# 4_Sensors.net
KiCad netlist of a schematic drawn in Altium Designer
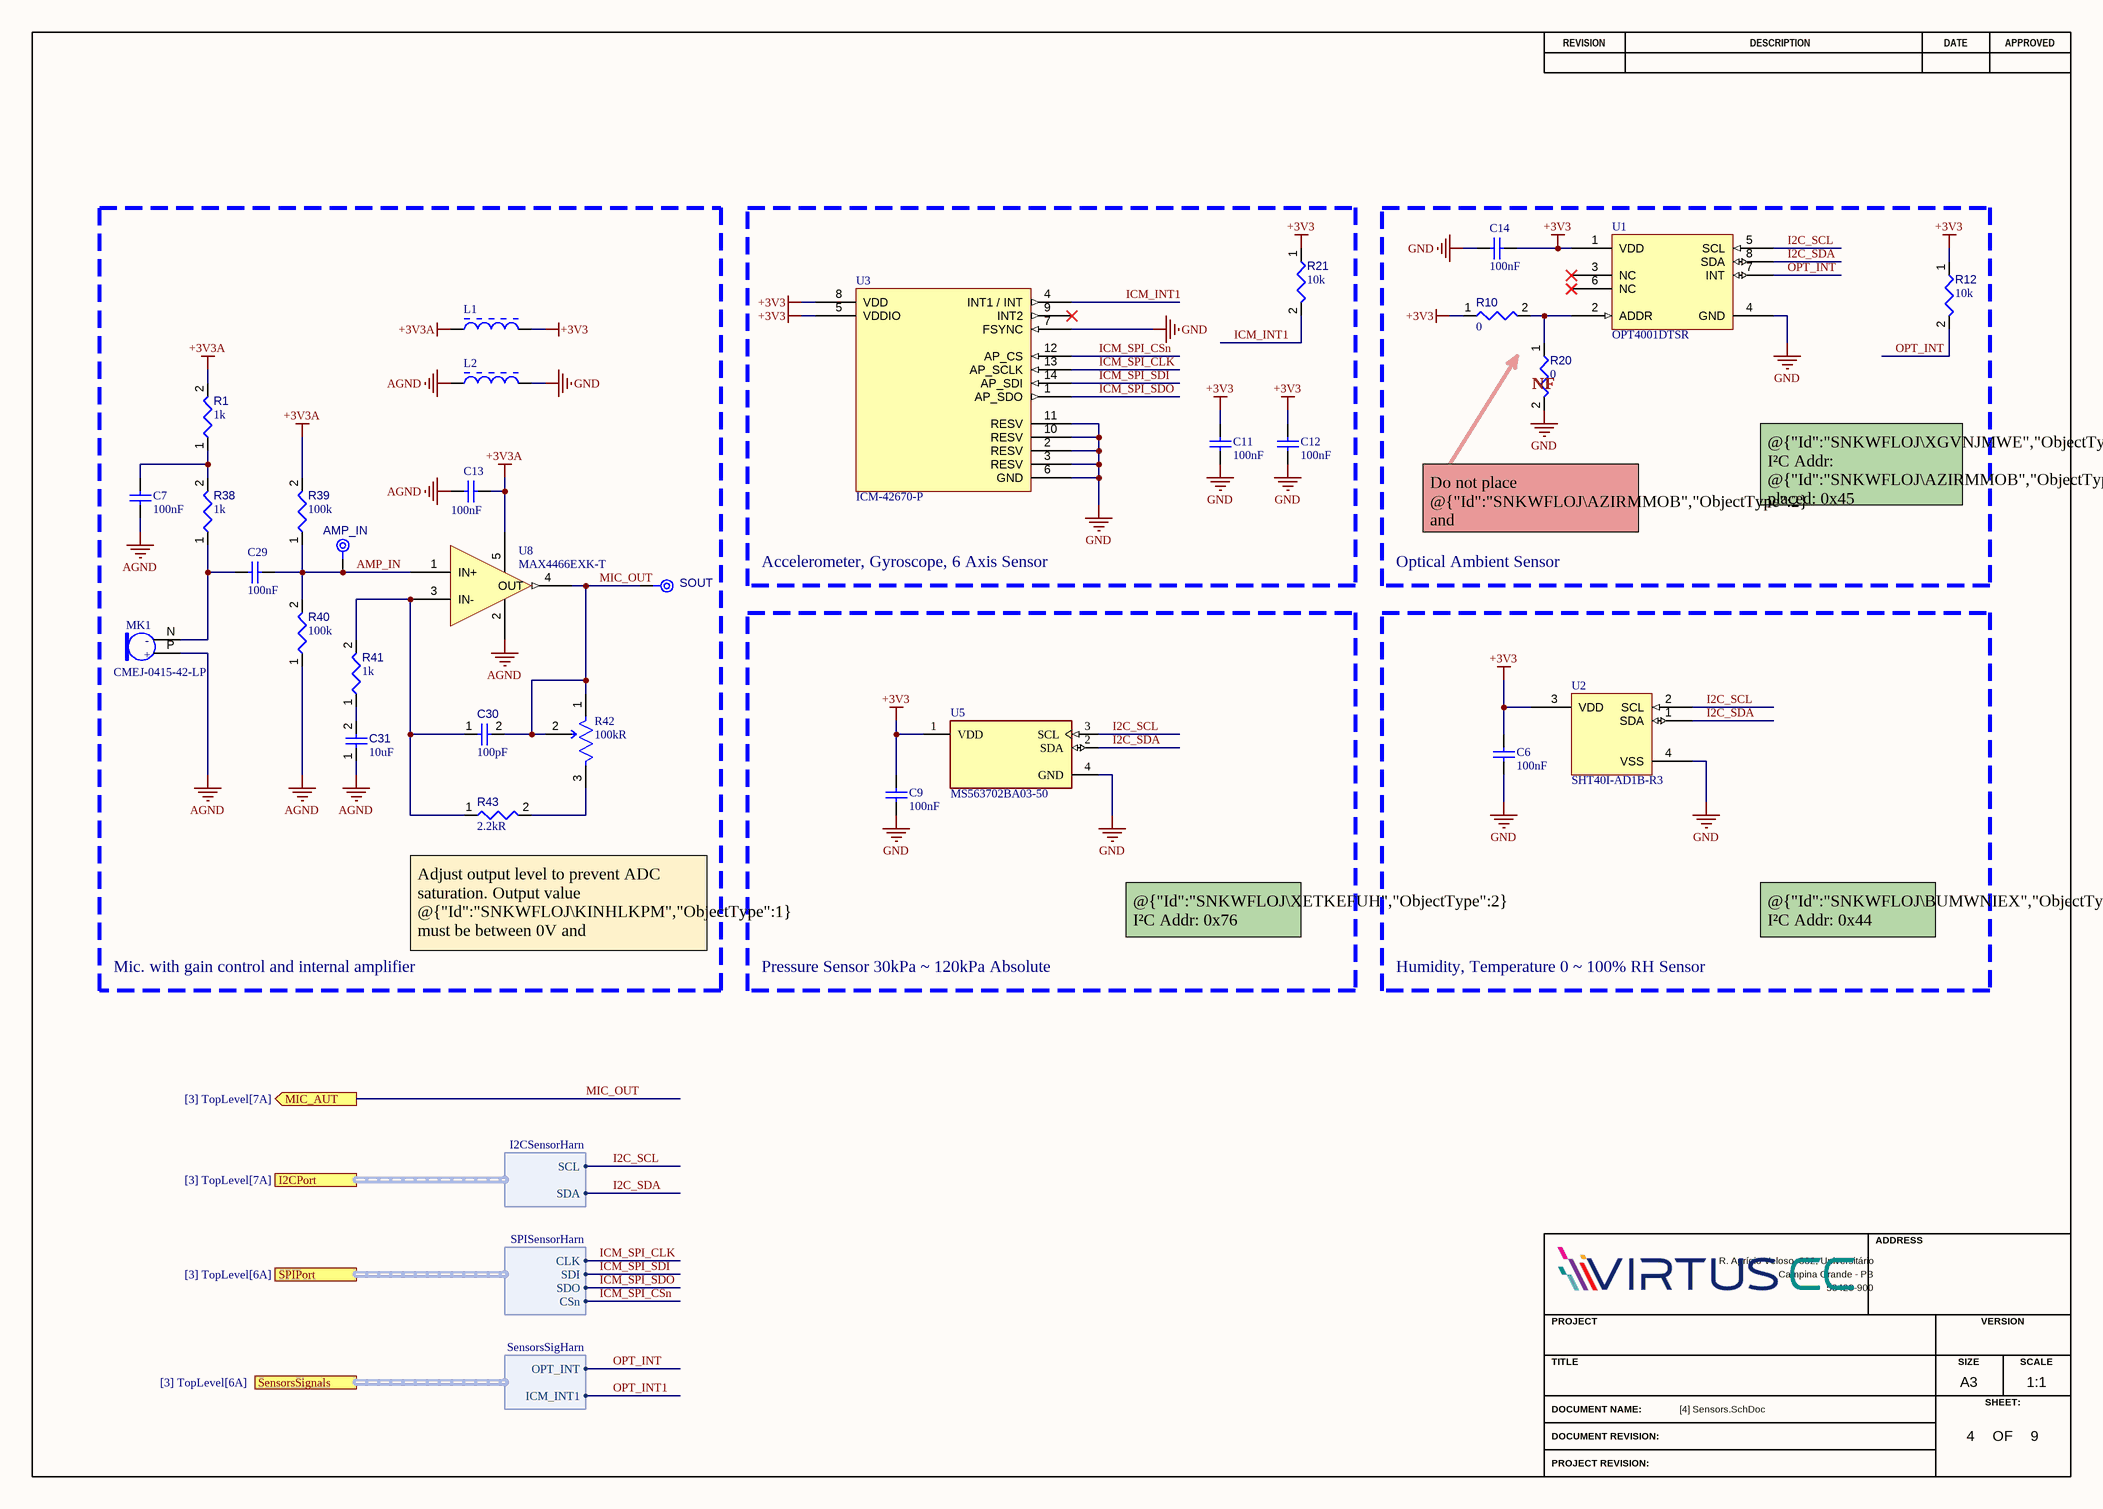
[diagram p0: [4] Sensors.SchDoc]

(export (version "E")
  (design (tool "Eeschema 10.0.6"))
  (components
    (comp (ref "AMP_IN")
      (value "TPAD6R")
      (footprint "TP06R")
      (description "0.6mm round")
      (libsource (lib "UFCG - Universidade Federal de Campina Grande") (part "CMP-001-0001-4"))
    )
    (comp (ref "C6")
      (value "100nF")
      (footprint "CAPC0603(1608)100_L")
      (description "Multilayer Ceramic Capacitor, 0.1 uF, 16 V, ± 20%, X7R, 0603 [1608 Metric]")
      (fields (field (name "TOLERANCE") "20%") (field (name "Comment") "VJ0603Y104MXJCW1BC"))
      (libsource (lib "UFCG - Universidade Federal de Campina Grande") (part "CAP"))
    )
    (comp (ref "C7")
      (value "100nF")
      (footprint "CAPC0603(1608)100_L")
      (description "Multilayer Ceramic Capacitor, 0.1 uF, 16 V, ± 20%, X7R, 0603 [1608 Metric]")
      (fields (field (name "TOLERANCE") "20%") (field (name "Comment") "VJ0603Y104MXJCW1BC"))
      (libsource (lib "UFCG - Universidade Federal de Campina Grande") (part "CAP"))
    )
    (comp (ref "C9")
      (value "100nF")
      (footprint "CAPC0603(1608)100_L")
      (description "Multilayer Ceramic Capacitor, 0.1 uF, 16 V, ± 20%, X7R, 0603 [1608 Metric]")
      (fields (field (name "TOLERANCE") "20%") (field (name "Comment") "VJ0603Y104MXJCW1BC"))
      (libsource (lib "UFCG - Universidade Federal de Campina Grande") (part "CAP"))
    )
    (comp (ref "C11")
      (value "100nF")
      (footprint "CAPC0603(1608)100_L")
      (description "Multilayer Ceramic Capacitor, 0.1 uF, 16 V, ± 20%, X7R, 0603 [1608 Metric]")
      (fields (field (name "TOLERANCE") "20%") (field (name "Comment") "VJ0603Y104MXJCW1BC"))
      (libsource (lib "UFCG - Universidade Federal de Campina Grande") (part "CAP"))
    )
    (comp (ref "C12")
      (value "100nF")
      (footprint "CAPC0603(1608)100_L")
      (description "Multilayer Ceramic Capacitor, 0.1 uF, 16 V, ± 20%, X7R, 0603 [1608 Metric]")
      (fields (field (name "TOLERANCE") "20%") (field (name "Comment") "VJ0603Y104MXJCW1BC"))
      (libsource (lib "UFCG - Universidade Federal de Campina Grande") (part "CAP"))
    )
    (comp (ref "C13")
      (value "100nF")
      (footprint "CAPC0603(1608)100_L")
      (description "Multilayer Ceramic Capacitor, 0.1 uF, 16 V, ± 20%, X7R, 0603 [1608 Metric]")
      (fields (field (name "TOLERANCE") "20%") (field (name "Comment") "VJ0603Y104MXJCW1BC"))
      (libsource (lib "UFCG - Universidade Federal de Campina Grande") (part "CAP"))
    )
    (comp (ref "C14")
      (value "100nF")
      (footprint "CAPC0603(1608)100_L")
      (description "Multilayer Ceramic Capacitor, 0.1 uF, 16 V, ± 20%, X7R, 0603 [1608 Metric]")
      (fields (field (name "TOLERANCE") "20%") (field (name "Comment") "VJ0603Y104MXJCW1BC"))
      (libsource (lib "UFCG - Universidade Federal de Campina Grande") (part "CAP"))
    )
    (comp (ref "C29")
      (value "100nF")
      (footprint "CAPC0603(1608)100_L")
      (description "Multilayer Ceramic Capacitor, 0.1 uF, 16 V, ± 20%, X7R, 0603 [1608 Metric]")
      (fields (field (name "TOLERANCE") "20%") (field (name "Comment") "VJ0603Y104MXJCW1BC"))
      (libsource (lib "UFCG - Universidade Federal de Campina Grande") (part "CAP"))
    )
    (comp (ref "C30")
      (value "100pF")
      (footprint "CAPC0603(1608)100_L")
      (description "Multilayer Ceramic Capacitor, 100 pF, 50 V, ï¿½ 10%, C0G (NP0), 0603 [1608 Metric]")
      (fields (field (name "TOLERANCE") "10%") (field (name "Comment") "C0603C101K5GACTU"))
      (libsource (lib "UFCG - Universidade Federal de Campina Grande") (part "CAP-NP-2"))
    )
    (comp (ref "C31")
      (value "10uF")
      (footprint "CAPC0603(1608)100_L")
      (description "Multilayer Ceramic Capacitor, 10 uF, 6.3 V, ± 20%, X5R, 0603 [1608 Metric]")
      (fields (field (name "TOLERANCE") "20%") (field (name "Comment") "GRM188R60J106ME47D"))
      (libsource (lib "UFCG - Universidade Federal de Campina Grande") (part "CAP-NP-2"))
    )
    (comp (ref "L1")
      (value "BLM21PG331SN1D")
      (footprint "INDC2013X105X50ML20T20")
      (fields (field (name "MANUFACTURER") "Murata") (field (name "TOLERANCE") "25%"))
      (libsource (lib "UFCG - Universidade Federal de Campina Grande") (part "IND-FB-2"))
    )
    (comp (ref "L2")
      (value "BLM21PG331SN1D")
      (footprint "INDC2013X105X50ML20T20")
      (fields (field (name "MANUFACTURER") "Murata") (field (name "TOLERANCE") "25%"))
      (libsource (lib "UFCG - Universidade Federal de Campina Grande") (part "IND-FB-2"))
    )
    (comp (ref "MK1")
      (value "CMEJ-0415-42-LP")
      (footprint "MIC_CMEJ-0415-42-LP")
      (description "4.0 mm, Omnidirectional, PCB Mount, 2.0 Vdc, Elecret Condenser Microphone")
      (fields (field (name "MF") "{'manufacturer': u'CUI'}"))
      (libsource (lib "UFCG - Universidade Federal de Campina Grande") (part "CMEJ-0415-42-LP"))
    )
    (comp (ref "R1")
      (value "1k")
      (footprint "RESC0603(1608)_L")
      (description "Chip Resistor, 1 KOhm, +/-1%, 0.1 W, -55 to 155 degC, 0603 (1608 Metric)")
      (fields (field (name "POWER") "100mW") (field (name "TOLERANCE") "1%"))
      (libsource (lib "UFCG - Universidade Federal de Campina Grande") (part "RES-2"))
    )
    (comp (ref "R10")
      (value "0")
      (footprint "RESC0603(1608)_L")
      (description "Chip Resistor, 0 Ohm, 0.1 W, -55 to 155 degC, 0603 (1608 Metric)")
      (fields (field (name "TOLERANCE") "5%") (field (name "POWER") "100mW"))
      (libsource (lib "UFCG - Universidade Federal de Campina Grande") (part "RES-2"))
    )
    (comp (ref "R12")
      (value "10k")
      (footprint "RESC0603(1608)_L")
      (description "Chip Resistor, 10 KOhm, +/- 1%, 01 W, -55 to 155 degC, 0603 (1608 Metric)")
      (fields (field (name "POWER") "100mW") (field (name "TOLERANCE") "1%"))
      (libsource (lib "UFCG - Universidade Federal de Campina Grande") (part "RES-2"))
    )
    (comp (ref "R20")
      (value "0")
      (footprint "RESC0603(1608)_L")
      (description "Chip Resistor, 0 Ohm, 0.1 W, -55 to 155 degC, 0603 (1608 Metric)")
      (fields (field (name "TOLERANCE") "5%") (field (name "POWER") "100mW"))
      (libsource (lib "UFCG - Universidade Federal de Campina Grande") (part "RES-2"))
    )
    (comp (ref "R21")
      (value "10k")
      (footprint "RESC0603(1608)_L")
      (description "Chip Resistor, 10 KOhm, +/- 1%, 01 W, -55 to 155 degC, 0603 (1608 Metric)")
      (fields (field (name "POWER") "100mW") (field (name "TOLERANCE") "1%"))
      (libsource (lib "UFCG - Universidade Federal de Campina Grande") (part "RES-2"))
    )
    (comp (ref "R38")
      (value "1k")
      (footprint "RESC0603(1608)_L")
      (description "Chip Resistor, 1 KOhm, +/-1%, 0.1 W, -55 to 155 degC, 0603 (1608 Metric)")
      (fields (field (name "POWER") "100mW") (field (name "TOLERANCE") "1%"))
      (libsource (lib "UFCG - Universidade Federal de Campina Grande") (part "RES-2"))
    )
    (comp (ref "R39")
      (value "100k")
      (footprint "RESC0603(1608)_L")
      (description "Chip Resistor, 100 KOhm, +/- 1%, 0.1 W, -55 to 155 degC, 0603 (1608 Metric)")
      (fields (field (name "TOLERANCE") "1%") (field (name "POWER") "100mW"))
      (libsource (lib "UFCG - Universidade Federal de Campina Grande") (part "RES-2"))
    )
    (comp (ref "R40")
      (value "100k")
      (footprint "RESC0603(1608)_L")
      (description "Chip Resistor, 100 KOhm, +/- 1%, 0.1 W, -55 to 155 degC, 0603 (1608 Metric)")
      (fields (field (name "TOLERANCE") "1%") (field (name "POWER") "100mW"))
      (libsource (lib "UFCG - Universidade Federal de Campina Grande") (part "RES-2"))
    )
    (comp (ref "R41")
      (value "1k")
      (footprint "RESC0603(1608)_L")
      (description "Chip Resistor, 1 KOhm, +/-1%, 0.1 W, -55 to 155 degC, 0603 (1608 Metric)")
      (fields (field (name "POWER") "100mW") (field (name "TOLERANCE") "1%"))
      (libsource (lib "UFCG - Universidade Federal de Campina Grande") (part "RES-2"))
    )
    (comp (ref "R42")
      (value "100kR")
      (footprint "FP-TC33X-2-MFG")
      (description "Cermet trimmer potentiometer, 100 kΩ, 0.1 W, SMD, on top, TC33X-2-104E")
      (fields (field (name "TOLERANCE") "25%") (field (name "Comment") "TC33X-2-104E"))
      (libsource (lib "UFCG - Universidade Federal de Campina Grande") (part "13357d81287629c2fd191d242cfa50c"))
    )
    (comp (ref "R43")
      (value "2.2kR")
      (footprint "RESC0603(1608)_L")
      (description "SMD Chip Resistor, 2.2 kOhm, ± 1%, 100 mW, 0603 [1608 Metric], Thick Film, General Purpose")
      (fields (field (name "TOLERANCE") "1%") (field (name "Comment") "CRCW06032K20FKEA"))
      (libsource (lib "UFCG - Universidade Federal de Campina Grande") (part "RES-2"))
    )
    (comp (ref "SOUT")
      (value "TPAD6R")
      (footprint "TP06R")
      (description "0.6mm round")
      (libsource (lib "UFCG - Universidade Federal de Campina Grande") (part "CMP-001-0001-4"))
    )
    (comp (ref "U1")
      (value "OPT4001DTSR")
      (footprint "SON50P130X60-8N")
      (description "High-speed high-precision digital ambient light sensor (ALS) 8-SOT-5X3 -40 to 85")
      (libsource (lib "UFCG - Universidade Federal de Campina Grande") (part "New symbol 1"))
    )
    (comp (ref "U2")
      (value "SHT40I-AD1B-R3")
      (footprint "QFN80P150X150X55-4N")
      (description "Humidity And Temperature Sensor")
      (libsource (lib "UFCG - Universidade Federal de Campina Grande") (part "SHT40I-AD1B-R3"))
    )
    (comp (ref "U3")
      (value "ICM-42670-P")
      (footprint "QFN50P300X250X81-14N")
      (description "Mems Module, 1.71-3.6 V, Lga-14 Rohs Compliant: Yes")
      (libsource (lib "UFCG - Universidade Federal de Campina Grande") (part "ICM-42670-P"))
    )
    (comp (ref "U5")
      (value "MS563702BA03-50")
      (footprint "FP-MS563702BA03-50-MFG")
      (description "Pressure Sensor, Barometric, 300 mbar, 1200 mbar, QFN, 8, -40 C")
      (libsource (lib "UFCG - Universidade Federal de Campina Grande") (part "74709a9a55dd6d6ee219151e6d8b12f"))
    )
    (comp (ref "U8")
      (value "MAX4466EXK-T")
      (footprint "SOT65P200X110-5N")
      (description "Audio Amp Microphone 1-CH Mono Class-AB 5-Pin SC-70 T/R")
      (libsource (lib "UFCG - Universidade Federal de Campina Grande") (part "MAX4466EXK-T"))
    )
  )
  (nets
    (net (code "4") (name "+3V3") (class "Default")
      (node (ref "C11") (pin "2") (pinfunction "2_2") (pintype "passive"))
      (node (ref "C12") (pin "2") (pinfunction "2_2") (pintype "passive"))
      (node (ref "C14") (pin "2") (pinfunction "2_2") (pintype "passive"))
      (node (ref "C6") (pin "2") (pinfunction "2_2") (pintype "passive"))
      (node (ref "C9") (pin "2") (pinfunction "2_2") (pintype "passive"))
      (node (ref "L1") (pin "2") (pinfunction "2_2") (pintype "passive"))
      (node (ref "R10") (pin "1") (pinfunction "1_1") (pintype "passive"))
      (node (ref "R12") (pin "1") (pinfunction "1_1") (pintype "passive"))
      (node (ref "R21") (pin "1") (pinfunction "1_1") (pintype "passive"))
      (node (ref "U1") (pin "1") (pinfunction "VDD_1") (pintype "power_in"))
      (node (ref "U2") (pin "3") (pinfunction "VDD_3") (pintype "power_in"))
      (node (ref "U3") (pin "5") (pinfunction "VDDIO_5") (pintype "power_in"))
      (node (ref "U3") (pin "8") (pinfunction "VDD_8") (pintype "power_in"))
      (node (ref "U5") (pin "1") (pinfunction "VDD_1") (pintype "power_in"))
    )
    (net (code "5") (name "+3V3A") (class "Default")
      (node (ref "C13") (pin "2") (pinfunction "2_2") (pintype "passive"))
      (node (ref "L1") (pin "1") (pinfunction "1_1") (pintype "passive"))
      (node (ref "R1") (pin "2") (pinfunction "2_2") (pintype "passive"))
      (node (ref "R39") (pin "2") (pinfunction "2_2") (pintype "passive"))
      (node (ref "U8") (pin "5") (pinfunction "VCC_5") (pintype "power_in"))
    )
    (net (code "6") (name "/AMP_IN") (class "Default")
      (node (ref "AMP_IN") (pin "1") (pinfunction "TP_1") (pintype "passive"))
      (node (ref "C29") (pin "2") (pinfunction "2_2") (pintype "passive"))
      (node (ref "R39") (pin "1") (pinfunction "1_1") (pintype "passive"))
      (node (ref "R40") (pin "2") (pinfunction "2_2") (pintype "passive"))
      (node (ref "U8") (pin "1") (pinfunction "IN+_1") (pintype "passive"))
    )
    (net (code "7") (name "/I2C_SCL") (class "Default")
      (node (ref "U1") (pin "5") (pinfunction "SCL_5") (pintype "input"))
      (node (ref "U2") (pin "2") (pinfunction "SCL_2") (pintype "input"))
      (node (ref "U5") (pin "3") (pinfunction "SCL_3") (pintype "input"))
    )
    (net (code "8") (name "/I2C_SDA") (class "Default")
      (node (ref "U1") (pin "8") (pinfunction "SDA_8") (pintype "bidirectional"))
      (node (ref "U2") (pin "1") (pinfunction "SDA_1") (pintype "bidirectional"))
      (node (ref "U5") (pin "2") (pinfunction "SDA_2") (pintype "bidirectional"))
    )
    (net (code "9") (name "/ICM_INT1") (class "Default")
      (node (ref "R21") (pin "2") (pinfunction "2_2") (pintype "passive"))
      (node (ref "U3") (pin "4") (pinfunction "INT1_/_INT_4") (pintype "output"))
    )
    (net (code "10") (name "/ICM_SPI_CLK") (class "Default")
      (node (ref "U3") (pin "13") (pinfunction "AP_SCLK_13") (pintype "input"))
    )
    (net (code "11") (name "/ICM_SPI_CSn") (class "Default")
      (node (ref "U3") (pin "12") (pinfunction "AP_CS_12") (pintype "input"))
    )
    (net (code "12") (name "/ICM_SPI_SDI") (class "Default")
      (node (ref "U3") (pin "14") (pinfunction "AP_SDI_14") (pintype "input"))
    )
    (net (code "13") (name "/ICM_SPI_SDO") (class "Default")
      (node (ref "U3") (pin "1") (pinfunction "AP_SDO_1") (pintype "output"))
    )
    (net (code "14") (name "/MIC_OUT") (class "Default")
      (node (ref "C30") (pin "2") (pinfunction "2_2") (pintype "passive"))
      (node (ref "R42") (pin "1") (pinfunction "CCW_1") (pintype "passive"))
      (node (ref "R42") (pin "2") (pinfunction "WIPER_2") (pintype "passive"))
      (node (ref "SOUT") (pin "1") (pinfunction "TP_1") (pintype "passive"))
      (node (ref "U8") (pin "4") (pinfunction "OUT_4") (pintype "output"))
    )
    (net (code "15") (name "/OPT_INT") (class "Default")
      (node (ref "R12") (pin "2") (pinfunction "2_2") (pintype "passive"))
      (node (ref "U1") (pin "7") (pinfunction "INT_7") (pintype "bidirectional"))
    )
    (net (code "20") (name "AGND") (class "Default")
      (node (ref "C13") (pin "1") (pinfunction "1_1") (pintype "passive"))
      (node (ref "C31") (pin "1") (pinfunction "1_1") (pintype "passive"))
      (node (ref "C7") (pin "1") (pinfunction "1_1") (pintype "passive"))
      (node (ref "L2") (pin "1") (pinfunction "1_1") (pintype "passive"))
      (node (ref "MK1") (pin "P") (pinfunction "OUTPUT_P") (pintype "passive"))
      (node (ref "R40") (pin "1") (pinfunction "1_1") (pintype "passive"))
      (node (ref "U8") (pin "2") (pinfunction "GND_2") (pintype "power_in"))
    )
    (net (code "21") (name "GND") (class "Default")
      (node (ref "C11") (pin "1") (pinfunction "1_1") (pintype "passive"))
      (node (ref "C12") (pin "1") (pinfunction "1_1") (pintype "passive"))
      (node (ref "C14") (pin "1") (pinfunction "1_1") (pintype "passive"))
      (node (ref "C6") (pin "1") (pinfunction "1_1") (pintype "passive"))
      (node (ref "C9") (pin "1") (pinfunction "1_1") (pintype "passive"))
      (node (ref "L2") (pin "2") (pinfunction "2_2") (pintype "passive"))
      (node (ref "R20") (pin "2") (pinfunction "2_2") (pintype "passive"))
      (node (ref "U1") (pin "4") (pinfunction "GND_4") (pintype "power_in"))
      (node (ref "U2") (pin "4") (pinfunction "VSS_4") (pintype "power_in"))
      (node (ref "U3") (pin "10") (pinfunction "RESV_10") (pintype "passive"))
      (node (ref "U3") (pin "11") (pinfunction "RESV_11") (pintype "passive"))
      (node (ref "U3") (pin "2") (pinfunction "RESV_2") (pintype "passive"))
      (node (ref "U3") (pin "3") (pinfunction "RESV_3") (pintype "passive"))
      (node (ref "U3") (pin "6") (pinfunction "GND_6") (pintype "power_in"))
      (node (ref "U3") (pin "7") (pinfunction "FSYNC_7") (pintype "input"))
      (node (ref "U5") (pin "4") (pinfunction "GND_4") (pintype "power_in"))
    )
    (net (code "22") (name "Net-(C7-Pad2)") (class "Default")
      (node (ref "C7") (pin "2") (pinfunction "2_2") (pintype "passive"))
      (node (ref "R1") (pin "1") (pinfunction "1_1") (pintype "passive"))
      (node (ref "R38") (pin "2") (pinfunction "2_2") (pintype "passive"))
    )
    (net (code "23") (name "Net-(C31-Pad2)") (class "Default")
      (node (ref "C31") (pin "2") (pinfunction "2_2") (pintype "passive"))
      (node (ref "R41") (pin "1") (pinfunction "1_1") (pintype "passive"))
    )
    (net (code "24") (name "Net-(MK1-GND)") (class "Default")
      (node (ref "C29") (pin "1") (pinfunction "1_1") (pintype "passive"))
      (node (ref "MK1") (pin "N") (pinfunction "GND_N") (pintype "passive"))
      (node (ref "R38") (pin "1") (pinfunction "1_1") (pintype "passive"))
    )
    (net (code "25") (name "Net-(R42-CW)") (class "Default")
      (node (ref "R42") (pin "3") (pinfunction "CW_3") (pintype "passive"))
      (node (ref "R43") (pin "2") (pinfunction "2_2") (pintype "passive"))
    )
    (net (code "26") (name "Net-(U1-ADDR)") (class "Default")
      (node (ref "R10") (pin "2") (pinfunction "2_2") (pintype "passive"))
      (node (ref "R20") (pin "1") (pinfunction "1_1") (pintype "passive"))
      (node (ref "U1") (pin "2") (pinfunction "ADDR_2") (pintype "input"))
    )
    (net (code "27") (name "Net-(U8-IN-)") (class "Default")
      (node (ref "C30") (pin "1") (pinfunction "1_1") (pintype "passive"))
      (node (ref "R41") (pin "2") (pinfunction "2_2") (pintype "passive"))
      (node (ref "R43") (pin "1") (pinfunction "1_1") (pintype "passive"))
      (node (ref "U8") (pin "3") (pinfunction "IN-_3") (pintype "passive"))
    )
    (net (code "28") (name "unconnected-(U1-NC-Pad3)") (class "Default")
      (node (ref "U1") (pin "3") (pinfunction "NC_3") (pintype "passive+no_connect"))
    )
    (net (code "29") (name "unconnected-(U1-NC-Pad6)") (class "Default")
      (node (ref "U1") (pin "6") (pinfunction "NC_6") (pintype "passive+no_connect"))
    )
    (net (code "30") (name "unconnected-(U3-INT2-Pad9)") (class "Default")
      (node (ref "U3") (pin "9") (pinfunction "INT2_9") (pintype "output+no_connect"))
    )
  )
)
